# Adafruit_HDC3021_Precision_Temperature_H.net
KiCad netlist of a schematic drawn in EAGLE
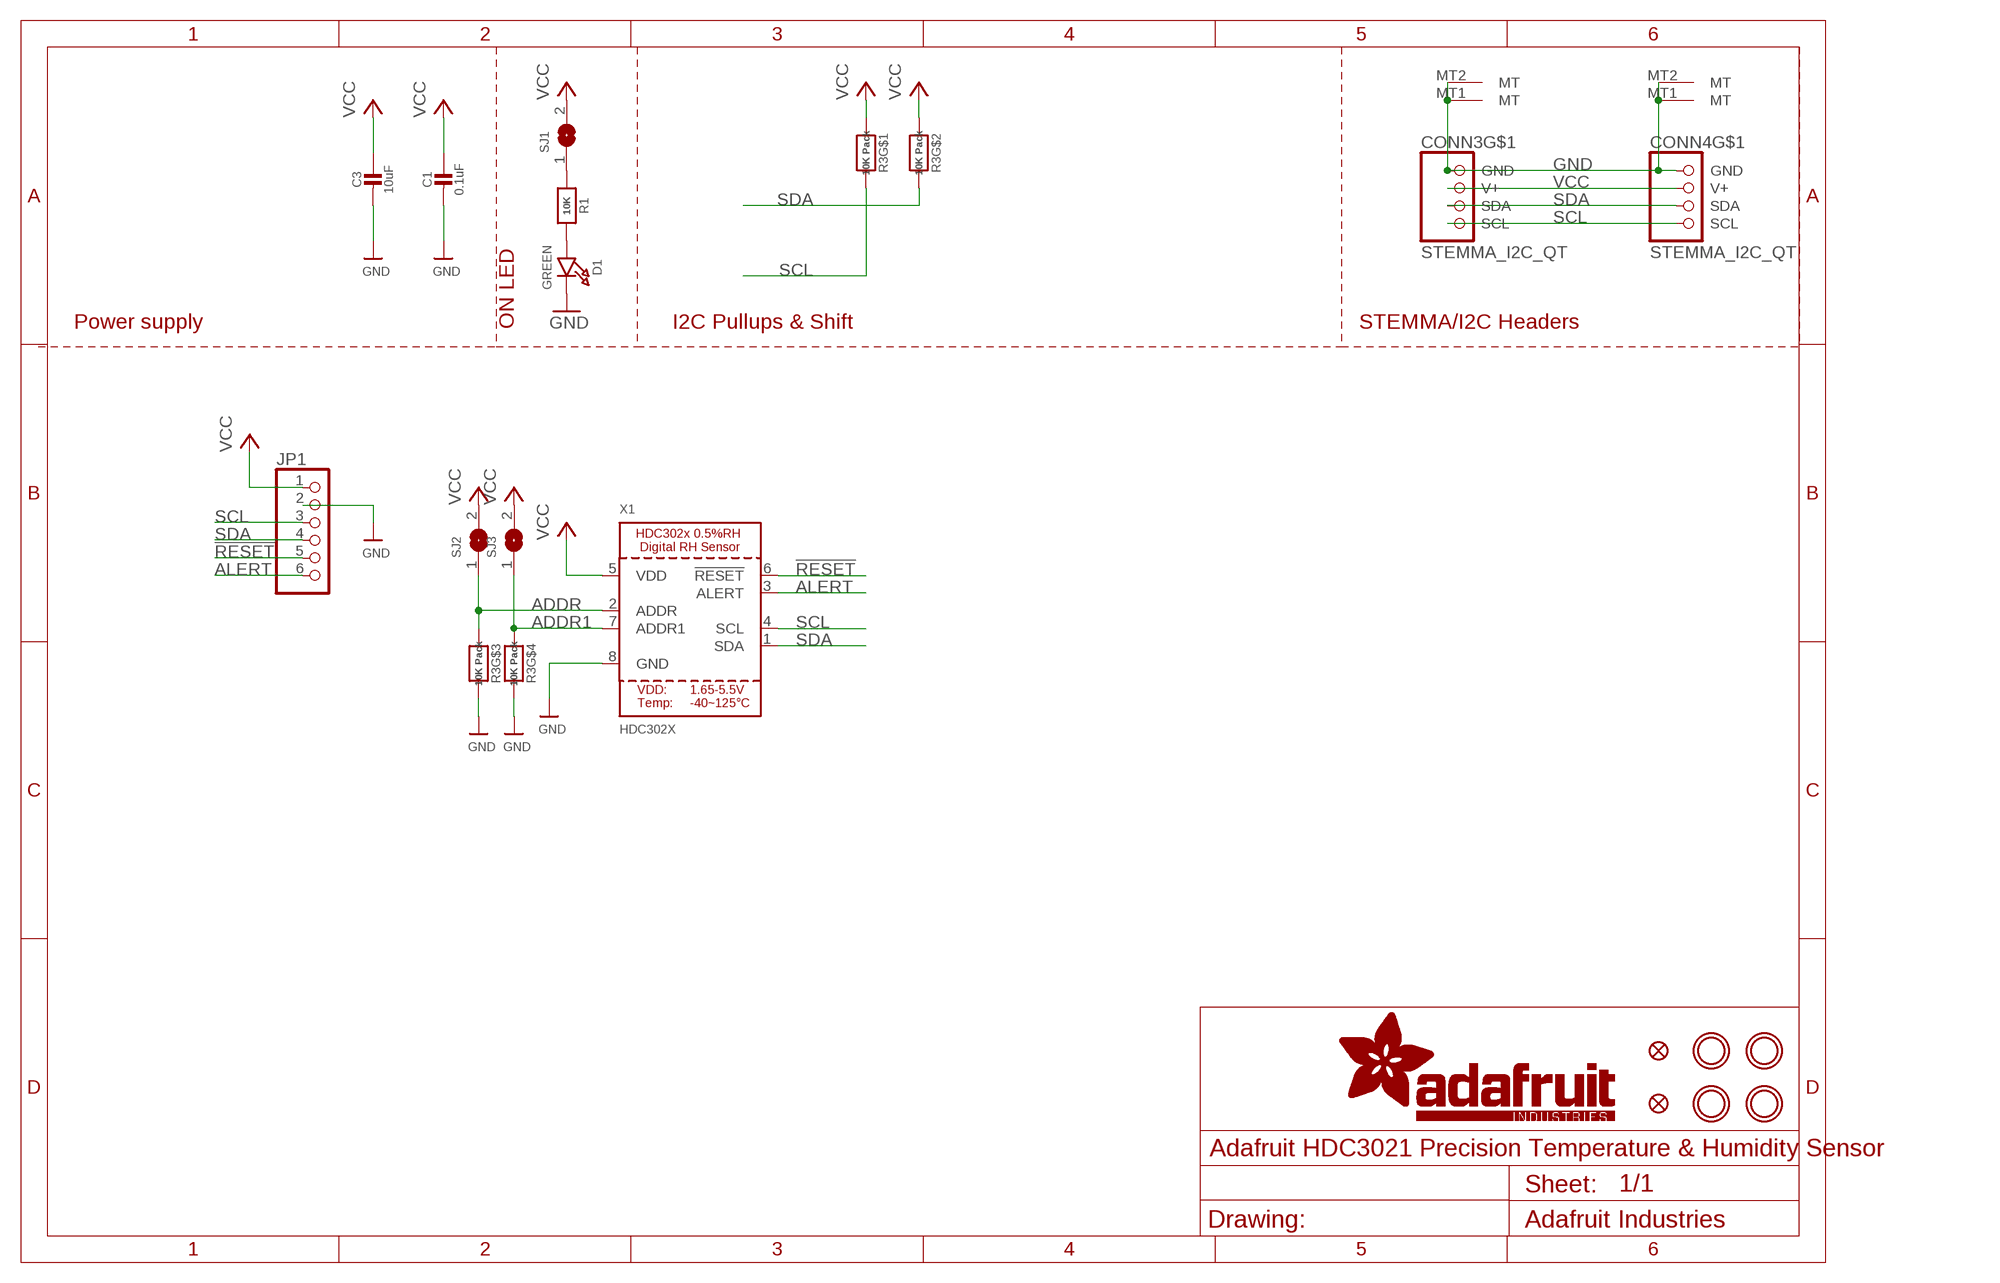
[diagram p0: schematic, sheet 1]

(export (version "E")
  (design (tool "Eeschema 10.0.6"))
  (components
    (comp (ref "C1")
      (value "0.1uF")
      (footprint "eagle-import:0603-NO")
      (libsource (lib "eagle-import") (part "CAP_CERAMIC0603_NO"))
    )
    (comp (ref "C3")
      (value "10uF")
      (footprint "eagle-import:0805-NO")
      (libsource (lib "eagle-import") (part "CAP_CERAMIC0805-NOOUTLINE"))
    )
    (comp (ref "CONN3")
      (value "STEMMA_I2C_QT")
      (footprint "eagle-import:JST_SH4")
      (libsource (lib "eagle-import") (part "STEMMA_I2C_QT"))
    )
    (comp (ref "CONN4")
      (value "STEMMA_I2C_QT")
      (footprint "eagle-import:JST_SH4")
      (libsource (lib "eagle-import") (part "STEMMA_I2C_QT"))
    )
    (comp (ref "D1")
      (value "GREEN")
      (footprint "eagle-import:CHIPLED_0603_NOOUTLINE")
      (libsource (lib "eagle-import") (part "LED0603_NOOUTLINE"))
    )
    (comp (ref "FID3")
      (value "FIDUCIAL_1MM")
      (footprint "eagle-import:FIDUCIAL_1MM")
      (libsource (lib "eagle-import") (part "FIDUCIAL_1MM"))
    )
    (comp (ref "FID4")
      (value "FIDUCIAL_1MM")
      (footprint "eagle-import:FIDUCIAL_1MM")
      (libsource (lib "eagle-import") (part "FIDUCIAL_1MM"))
    )
    (comp (ref "JP1")
      (value "HEADER-1X670MIL")
      (footprint "eagle-import:1X06_ROUND_70")
      (libsource (lib "eagle-import") (part "HEADER-1X670MIL"))
    )
    (comp (ref "R1")
      (value "10K")
      (footprint "eagle-import:0603-NO")
      (libsource (lib "eagle-import") (part "RESISTOR_0603_NOOUT"))
    )
    (comp (ref "R3")
      (value "10K Pack")
      (footprint "eagle-import:RESPACK_4X0603")
      (libsource (lib "eagle-import") (part "RESISTOR_4PACK"))
    )
    (comp (ref "SJ1")
      (value "SOLDERJUMPERCLOSED")
      (footprint "eagle-import:SOLDERJUMPER_CLOSEDWIRE")
      (libsource (lib "eagle-import") (part "SOLDERJUMPERCLOSED"))
    )
    (comp (ref "SJ2")
      (value "SOLDERJUMPER")
      (footprint "eagle-import:SOLDERJUMPER_ARROW_NOPASTE")
      (libsource (lib "eagle-import") (part "SOLDERJUMPER"))
    )
    (comp (ref "SJ3")
      (value "SOLDERJUMPER")
      (footprint "eagle-import:SOLDERJUMPER_ARROW_NOPASTE")
      (libsource (lib "eagle-import") (part "SOLDERJUMPER"))
    )
    (comp (ref "U$1")
      (value "MOUNTINGHOLE2.5")
      (footprint "eagle-import:MOUNTINGHOLE_2.5_PLATED")
      (libsource (lib "eagle-import") (part "MOUNTINGHOLE2.5"))
    )
    (comp (ref "U$17")
      (value "MOUNTINGHOLE2.5")
      (footprint "eagle-import:MOUNTINGHOLE_2.5_PLATED")
      (libsource (lib "eagle-import") (part "MOUNTINGHOLE2.5"))
    )
    (comp (ref "U$19")
      (value "MOUNTINGHOLE2.5")
      (footprint "eagle-import:MOUNTINGHOLE_2.5_PLATED")
      (libsource (lib "eagle-import") (part "MOUNTINGHOLE2.5"))
    )
    (comp (ref "U$21")
      (value "MOUNTINGHOLE2.5")
      (footprint "eagle-import:MOUNTINGHOLE_2.5_PLATED")
      (libsource (lib "eagle-import") (part "MOUNTINGHOLE2.5"))
    )
    (comp (ref "X1")
      (value "HDC302X")
      (footprint "eagle-import:WSON8")
      (libsource (lib "eagle-import") (part "HDC302X"))
    )
  )
  (nets
    (net (code "1") (name "/ADDR") (class "Default")
      (node (ref "R3") (pin "3") (pinfunction "1_3") (pintype "passive"))
      (node (ref "SJ2") (pin "1") (pinfunction "1_1") (pintype "passive"))
      (node (ref "X1") (pin "2") (pinfunction "ADDR_2") (pintype "input"))
    )
    (net (code "2") (name "/ADDR1") (class "Default")
      (node (ref "R3") (pin "4") (pinfunction "1_4") (pintype "passive"))
      (node (ref "SJ3") (pin "1") (pinfunction "1_1") (pintype "passive"))
      (node (ref "X1") (pin "7") (pinfunction "ADDR1_7") (pintype "input"))
    )
    (net (code "3") (name "/ALERT") (class "Default")
      (node (ref "JP1") (pin "6") (pinfunction "6_6") (pintype "passive"))
      (node (ref "X1") (pin "3") (pinfunction "ALERT_3") (pintype "output"))
    )
    (net (code "4") (name "/SCL") (class "Default")
      (node (ref "CONN3") (pin "4") (pinfunction "SCL_4") (pintype "passive"))
      (node (ref "CONN4") (pin "4") (pinfunction "SCL_4") (pintype "passive"))
      (node (ref "JP1") (pin "3") (pinfunction "3_3") (pintype "passive"))
      (node (ref "R3") (pin "8") (pinfunction "2_8") (pintype "passive"))
      (node (ref "X1") (pin "4") (pinfunction "SCL_4") (pintype "input"))
    )
    (net (code "5") (name "/SDA") (class "Default")
      (node (ref "CONN3") (pin "3") (pinfunction "SDA_3") (pintype "passive"))
      (node (ref "CONN4") (pin "3") (pinfunction "SDA_3") (pintype "passive"))
      (node (ref "JP1") (pin "4") (pinfunction "4_4") (pintype "passive"))
      (node (ref "R3") (pin "7") (pinfunction "2_7") (pintype "passive"))
      (node (ref "X1") (pin "1") (pinfunction "SDA_1") (pintype "bidirectional"))
    )
    (net (code "6") (name "/~{RESET}") (class "Default")
      (node (ref "JP1") (pin "5") (pinfunction "5_5") (pintype "passive"))
      (node (ref "X1") (pin "6") (pinfunction "~{RESET}_6") (pintype "input"))
    )
    (net (code "7") (name "GND") (class "Default")
      (node (ref "C1") (pin "2") (pinfunction "2_2") (pintype "passive"))
      (node (ref "C3") (pin "2") (pinfunction "2_2") (pintype "passive"))
      (node (ref "CONN3") (pin "1") (pinfunction "GND_1") (pintype "passive"))
      (node (ref "CONN3") (pin "MT1") (pinfunction "MT_MT1") (pintype "bidirectional"))
      (node (ref "CONN3") (pin "MT2") (pinfunction "MT_MT2") (pintype "bidirectional"))
      (node (ref "CONN4") (pin "1") (pinfunction "GND_1") (pintype "passive"))
      (node (ref "CONN4") (pin "MT1") (pinfunction "MT_MT1") (pintype "bidirectional"))
      (node (ref "CONN4") (pin "MT2") (pinfunction "MT_MT2") (pintype "bidirectional"))
      (node (ref "D1") (pin "C") (pinfunction "C_C") (pintype "passive"))
      (node (ref "JP1") (pin "2") (pinfunction "2_2") (pintype "passive"))
      (node (ref "R3") (pin "5") (pinfunction "2_5") (pintype "passive"))
      (node (ref "R3") (pin "6") (pinfunction "2_6") (pintype "passive"))
      (node (ref "X1") (pin "8") (pinfunction "GND_8") (pintype "power_in"))
    )
    (net (code "8") (name "Net-(D1-PadA)") (class "Default")
      (node (ref "D1") (pin "A") (pinfunction "A_A") (pintype "passive"))
      (node (ref "R1") (pin "2") (pinfunction "2_2") (pintype "passive"))
    )
    (net (code "9") (name "Net-(R1-Pad1)") (class "Default")
      (node (ref "R1") (pin "1") (pinfunction "1_1") (pintype "passive"))
      (node (ref "SJ1") (pin "1") (pinfunction "1_1") (pintype "passive"))
    )
    (net (code "10") (name "VCC") (class "Default")
      (node (ref "C1") (pin "1") (pinfunction "1_1") (pintype "passive"))
      (node (ref "C3") (pin "1") (pinfunction "1_1") (pintype "passive"))
      (node (ref "CONN3") (pin "2") (pinfunction "V+_2") (pintype "passive"))
      (node (ref "CONN4") (pin "2") (pinfunction "V+_2") (pintype "passive"))
      (node (ref "JP1") (pin "1") (pinfunction "1_1") (pintype "passive"))
      (node (ref "R3") (pin "1") (pinfunction "1_1") (pintype "passive"))
      (node (ref "R3") (pin "2") (pinfunction "1_2") (pintype "passive"))
      (node (ref "SJ1") (pin "2") (pinfunction "2_2") (pintype "passive"))
      (node (ref "SJ2") (pin "2") (pinfunction "2_2") (pintype "passive"))
      (node (ref "SJ3") (pin "2") (pinfunction "2_2") (pintype "passive"))
      (node (ref "X1") (pin "5") (pinfunction "VDD_5") (pintype "power_in"))
    )
  )
)
